# POWER.net
KiCad netlist of a schematic drawn in Altium Designer
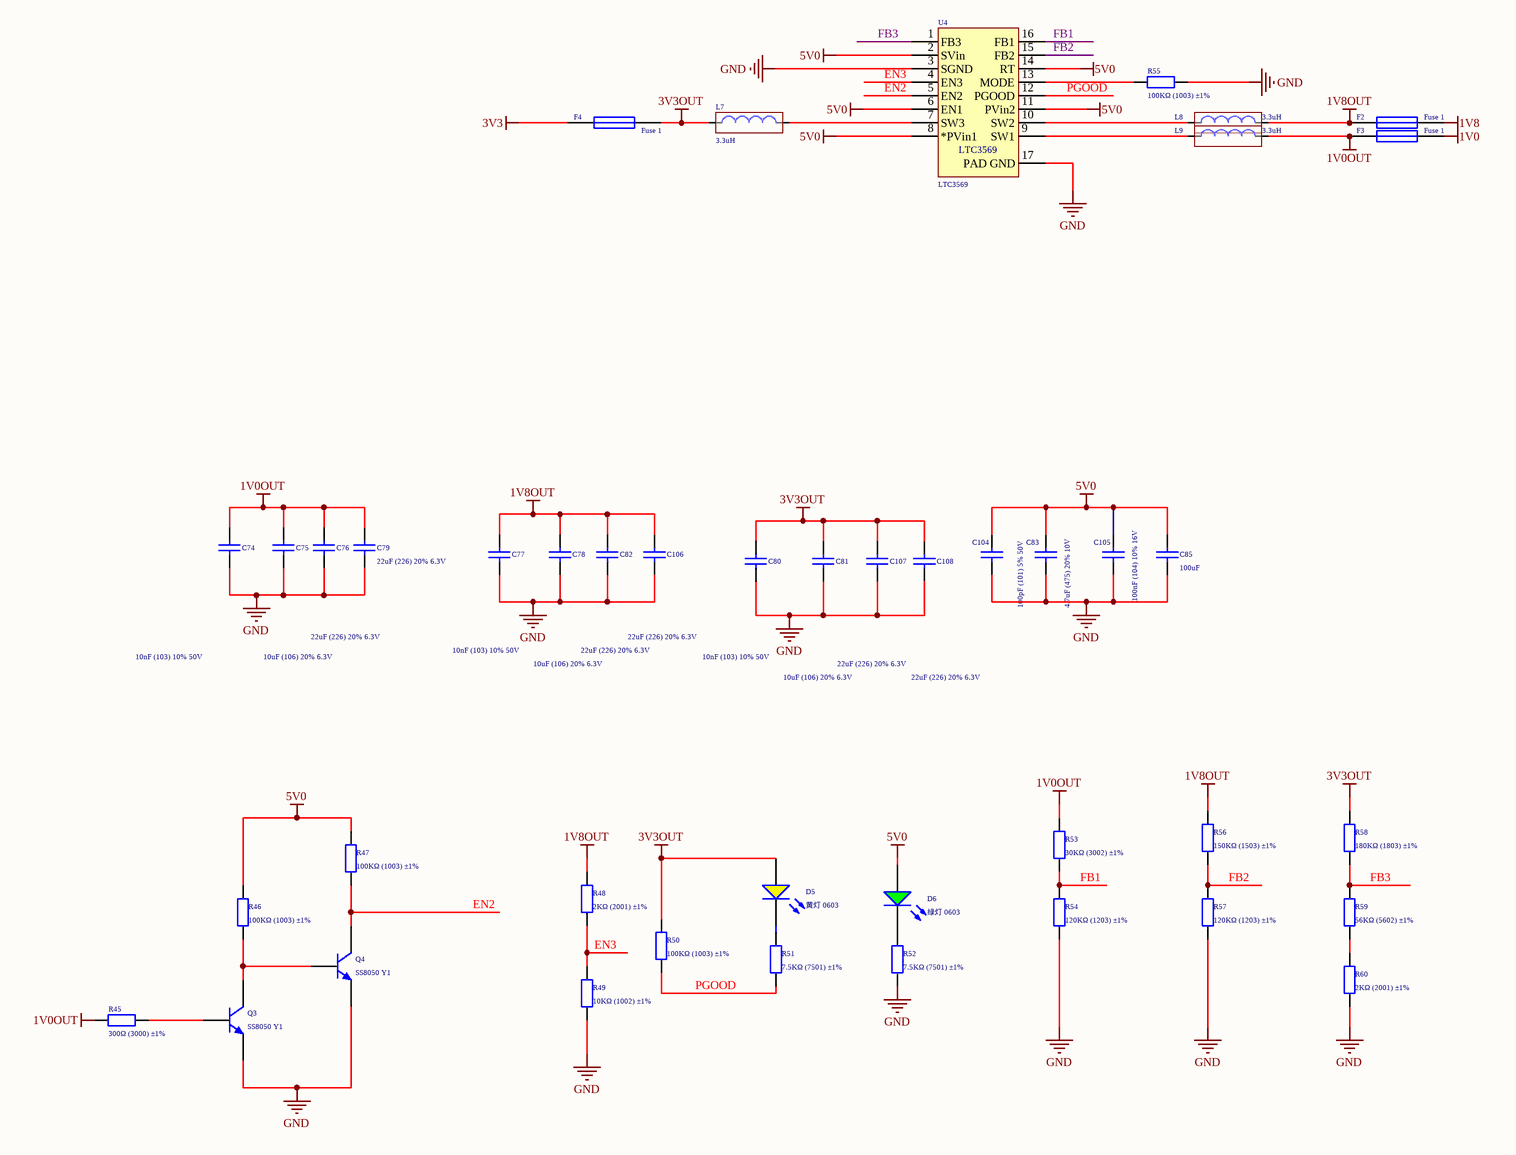
[diagram p0: POWER.SchDoc]

(export (version "E")
  (design (tool "Eeschema 10.0.6"))
  (components
    (comp (ref "C74")
      (value "10nF (103) 10% 50V")
      (footprint "0402_C")
      (description "贴片电容")
      (libsource (lib "Miscellaneous Devices LC") (part "0402 10nF (103) 10% 50V"))
    )
    (comp (ref "C75")
      (value "10uF (106) 20% 6.3V")
      (footprint "0402_C")
      (description "贴片电容")
      (libsource (lib "Miscellaneous Devices LC") (part "0402 10uF (106) 20% 6.3V"))
    )
    (comp (ref "C76")
      (value "22uF (226) 20% 6.3V")
      (footprint "0603_C")
      (description "贴片电容")
      (libsource (lib "Miscellaneous Devices LC") (part "0603 22uF (226) 20% 6.3V"))
    )
    (comp (ref "C77")
      (value "10nF (103) 10% 50V")
      (footprint "0402_C")
      (description "贴片电容")
      (libsource (lib "Miscellaneous Devices LC") (part "0402 10nF (103) 10% 50V"))
    )
    (comp (ref "C78")
      (value "10uF (106) 20% 6.3V")
      (footprint "0402_C")
      (description "贴片电容")
      (libsource (lib "Miscellaneous Devices LC") (part "0402 10uF (106) 20% 6.3V"))
    )
    (comp (ref "C79")
      (value "22uF (226) 20% 6.3V")
      (footprint "0603_C")
      (description "贴片电容")
      (libsource (lib "Miscellaneous Devices LC") (part "0603 22uF (226) 20% 6.3V"))
    )
    (comp (ref "C80")
      (value "10nF (103) 10% 50V")
      (footprint "0402_C")
      (description "贴片电容")
      (libsource (lib "Miscellaneous Devices LC") (part "0402 10nF (103) 10% 50V"))
    )
    (comp (ref "C81")
      (value "10uF (106) 20% 6.3V")
      (footprint "0402_C")
      (description "贴片电容")
      (libsource (lib "Miscellaneous Devices LC") (part "0402 10uF (106) 20% 6.3V"))
    )
    (comp (ref "C82")
      (value "22uF (226) 20% 6.3V")
      (footprint "0603_C")
      (description "贴片电容")
      (libsource (lib "Miscellaneous Devices LC") (part "0603 22uF (226) 20% 6.3V"))
    )
    (comp (ref "C83")
      (value "4.7uF (475) 20% 10V")
      (footprint "0402_C")
      (description "贴片电容")
      (libsource (lib "Miscellaneous Devices LC") (part "0402 4.7uF (475) 20% 10V"))
    )
    (comp (ref "C85")
      (value "100uF")
      (footprint "LC-1206")
      (description "贴片电容")
      (fields (field (name "Comment") "Cap") (field (name "PUBLISHER") "Altium Limited"))
      (libsource (lib "Sparks") (part "Cap"))
    )
    (comp (ref "C104")
      (value "100pF (101) 5% 50V")
      (footprint "0402_C")
      (description "贴片电容")
      (libsource (lib "Miscellaneous Devices LC") (part "0402 100pF (101) 5% 50V"))
    )
    (comp (ref "C105")
      (value "100nF (104) 10% 16V")
      (footprint "0402_C")
      (description "贴片电容")
      (libsource (lib "Miscellaneous Devices LC") (part "0402 100nF (104) 10% 16V"))
    )
    (comp (ref "C106")
      (value "22uF (226) 20% 6.3V")
      (footprint "0603_C")
      (description "贴片电容")
      (libsource (lib "Miscellaneous Devices LC") (part "0603 22uF (226) 20% 6.3V"))
    )
    (comp (ref "C107")
      (value "22uF (226) 20% 6.3V")
      (footprint "0603_C")
      (description "贴片电容")
      (libsource (lib "Miscellaneous Devices LC") (part "0603 22uF (226) 20% 6.3V"))
    )
    (comp (ref "C108")
      (value "22uF (226) 20% 6.3V")
      (footprint "0603_C")
      (description "贴片电容")
      (libsource (lib "Miscellaneous Devices LC") (part "0603 22uF (226) 20% 6.3V"))
    )
    (comp (ref "D5")
      (value "黄灯 0603")
      (footprint "0603_LED_S1")
      (description "发光二极管")
      (libsource (lib "Miscellaneous Devices LC") (part "0603 黄灯"))
    )
    (comp (ref "D6")
      (value "绿灯 0603")
      (footprint "0603_LED_S1")
      (description "发光二极管")
      (libsource (lib "Miscellaneous Devices LC") (part "0603 绿灯"))
    )
    (comp (ref "F2")
      (value "Fuse 1")
      (footprint "1206")
      (description "Fuse")
      (fields (field (name "PUBLISHER") "Altium Limited"))
      (libsource (lib "Miscellaneous Devices") (part "Fuse 1"))
    )
    (comp (ref "F3")
      (value "Fuse 1")
      (footprint "1206")
      (description "Fuse")
      (fields (field (name "PUBLISHER") "Altium Limited"))
      (libsource (lib "Miscellaneous Devices") (part "Fuse 1"))
    )
    (comp (ref "F4")
      (value "Fuse 1")
      (footprint "1206")
      (description "Fuse")
      (fields (field (name "PUBLISHER") "Altium Limited"))
      (libsource (lib "Miscellaneous Devices") (part "Fuse 1"))
    )
    (comp (ref "L7")
      (value "3.3uH")
      (footprint "LC-1210")
      (description "Inductor")
      (libsource (lib "2号库") (part "Inductor_1"))
    )
    (comp (ref "L8")
      (value "3.3uH")
      (footprint "LC-1210")
      (description "Inductor")
      (libsource (lib "2号库") (part "Inductor_1"))
    )
    (comp (ref "L9")
      (value "3.3uH")
      (footprint "LC-1210")
      (description "Inductor")
      (libsource (lib "2号库") (part "Inductor_1"))
    )
    (comp (ref "Q3")
      (value "SS8050 Y1")
      (footprint "SOT-23(SOT-23-3)")
      (description "三极管")
      (libsource (lib "Transistor_NPN") (part "SOT-23 SS8050 Y1"))
    )
    (comp (ref "Q4")
      (value "SS8050 Y1")
      (footprint "SOT-23(SOT-23-3)")
      (description "三极管")
      (libsource (lib "Transistor_NPN") (part "SOT-23 SS8050 Y1"))
    )
    (comp (ref "R45")
      (value "300Ω (3000) ±1%")
      (footprint "0402_R")
      (description "贴片电阻")
      (libsource (lib "Miscellaneous Devices LC") (part "0402 300Ω (3000) 1%"))
    )
    (comp (ref "R46")
      (value "100KΩ (1003) ±1%")
      (footprint "0402_R")
      (description "贴片电阻")
      (libsource (lib "Miscellaneous Devices LC") (part "0402 100KΩ (1003) 1%"))
    )
    (comp (ref "R47")
      (value "100KΩ (1003) ±1%")
      (footprint "0402_R")
      (description "贴片电阻")
      (libsource (lib "Miscellaneous Devices LC") (part "0402 100KΩ (1003) 1%"))
    )
    (comp (ref "R48")
      (value "2KΩ (2001) ±1%")
      (footprint "0402_R")
      (description "贴片电阻")
      (libsource (lib "Miscellaneous Devices LC") (part "0402 2KΩ (2001) 1%"))
    )
    (comp (ref "R49")
      (value "10KΩ (1002) ±1%")
      (footprint "0402_R")
      (description "贴片电阻")
      (libsource (lib "Miscellaneous Devices LC") (part "0402 10KΩ (1002) 1%"))
    )
    (comp (ref "R50")
      (value "100KΩ (1003) ±1%")
      (footprint "0402_R")
      (description "贴片电阻")
      (libsource (lib "Miscellaneous Devices LC") (part "0402 100KΩ (1003) 1%"))
    )
    (comp (ref "R51")
      (value "7.5KΩ (7501) ±1%")
      (footprint "0402_R")
      (description "贴片电阻")
      (libsource (lib "Miscellaneous Devices LC") (part "0402 7.5KΩ (7501) 1%"))
    )
    (comp (ref "R52")
      (value "7.5KΩ (7501) ±1%")
      (footprint "0402_R")
      (description "贴片电阻")
      (libsource (lib "Miscellaneous Devices LC") (part "0402 7.5KΩ (7501) 1%"))
    )
    (comp (ref "R53")
      (value "30KΩ (3002) ±1%")
      (footprint "0603_R")
      (description "贴片电阻")
      (libsource (lib "RES") (part "0603 30KΩ (3002) 1%"))
    )
    (comp (ref "R54")
      (value "120KΩ (1203) ±1%")
      (footprint "0402_R")
      (description "贴片电阻")
      (libsource (lib "Miscellaneous Devices LC") (part "0402 120KΩ (1203) 1%"))
    )
    (comp (ref "R55")
      (value "100KΩ (1003) ±1%")
      (footprint "0402_R")
      (description "贴片电阻")
      (libsource (lib "") (part "0402 100KΩ (1003) 1%_1"))
    )
    (comp (ref "R56")
      (value "150KΩ (1503) ±1%")
      (footprint "0402_R")
      (description "贴片电阻")
      (libsource (lib "Miscellaneous Devices LC") (part "0402 150KΩ (1503) 1%"))
    )
    (comp (ref "R57")
      (value "120KΩ (1203) ±1%")
      (footprint "0402_R")
      (description "贴片电阻")
      (libsource (lib "Miscellaneous Devices LC") (part "0402 120KΩ (1203) 1%"))
    )
    (comp (ref "R58")
      (value "180KΩ (1803) ±1%")
      (footprint "0603_R")
      (description "贴片电阻")
      (libsource (lib "Miscellaneous Devices LC") (part "0603 180KΩ (1803) 1%"))
    )
    (comp (ref "R59")
      (value "56KΩ (5602) ±1%")
      (footprint "0402_R")
      (description "贴片电阻")
      (libsource (lib "Miscellaneous Devices LC") (part "0402 56KΩ (5602) 1%"))
    )
    (comp (ref "R60")
      (value "2KΩ (2001) ±1%")
      (footprint "0402_R")
      (description "贴片电阻")
      (libsource (lib "Miscellaneous Devices LC") (part "0402 2KΩ (2001) 1%"))
    )
    (comp (ref "U4")
      (value "LTC3569")
      (footprint "SOP127P600-16N")
      (libsource (lib "Schlib") (part "LTC3569"))
    )
  )
  (nets
    (net (code "1") (name "/EN2") (class "Default")
      (node (ref "Q4") (pin "3") (pinfunction "C_3") (pintype "passive"))
      (node (ref "R47") (pin "1") (pinfunction "1_1") (pintype "passive"))
      (node (ref "U4") (pin "5") (pinfunction "EN2_5") (pintype "passive"))
    )
    (net (code "2") (name "/EN3") (class "Default")
      (node (ref "R48") (pin "1") (pinfunction "1_1") (pintype "passive"))
      (node (ref "R49") (pin "2") (pinfunction "2_2") (pintype "passive"))
      (node (ref "U4") (pin "4") (pinfunction "EN3_4") (pintype "passive"))
    )
    (net (code "3") (name "/FB1") (class "Default")
      (node (ref "R53") (pin "1") (pinfunction "1_1") (pintype "passive"))
      (node (ref "R54") (pin "2") (pinfunction "2_2") (pintype "passive"))
      (node (ref "U4") (pin "16") (pinfunction "FB1_16") (pintype "passive"))
    )
    (net (code "4") (name "/FB2") (class "Default")
      (node (ref "R56") (pin "1") (pinfunction "1_1") (pintype "passive"))
      (node (ref "R57") (pin "2") (pinfunction "2_2") (pintype "passive"))
      (node (ref "U4") (pin "15") (pinfunction "FB2_15") (pintype "passive"))
    )
    (net (code "5") (name "/FB3") (class "Default")
      (node (ref "R58") (pin "1") (pinfunction "1_1") (pintype "passive"))
      (node (ref "R59") (pin "2") (pinfunction "2_2") (pintype "passive"))
      (node (ref "U4") (pin "1") (pinfunction "FB3_1") (pintype "passive"))
    )
    (net (code "6") (name "/PGOOD") (class "Default")
      (node (ref "R50") (pin "1") (pinfunction "1_1") (pintype "passive"))
      (node (ref "R51") (pin "1") (pinfunction "1_1") (pintype "passive"))
      (node (ref "U4") (pin "12") (pinfunction "PGOOD_12") (pintype "passive"))
    )
    (net (code "7") (name "1V0") (class "Default")
      (node (ref "F3") (pin "1") (pinfunction "1_1") (pintype "passive"))
    )
    (net (code "8") (name "1V0OUT") (class "Default")
      (node (ref "C74") (pin "2") (pinfunction "2_2") (pintype "passive"))
      (node (ref "C75") (pin "2") (pinfunction "2_2") (pintype "passive"))
      (node (ref "C76") (pin "2") (pinfunction "2_2") (pintype "passive"))
      (node (ref "C79") (pin "2") (pinfunction "2_2") (pintype "passive"))
      (node (ref "F3") (pin "2") (pinfunction "2_2") (pintype "passive"))
      (node (ref "L9") (pin "2") (pinfunction "2_2") (pintype "passive"))
      (node (ref "R45") (pin "1") (pinfunction "1_1") (pintype "passive"))
      (node (ref "R53") (pin "2") (pinfunction "2_2") (pintype "passive"))
    )
    (net (code "9") (name "1V8") (class "Default")
      (node (ref "F2") (pin "1") (pinfunction "1_1") (pintype "passive"))
    )
    (net (code "10") (name "1V8OUT") (class "Default")
      (node (ref "C106") (pin "2") (pinfunction "2_2") (pintype "passive"))
      (node (ref "C77") (pin "2") (pinfunction "2_2") (pintype "passive"))
      (node (ref "C78") (pin "2") (pinfunction "2_2") (pintype "passive"))
      (node (ref "C82") (pin "2") (pinfunction "2_2") (pintype "passive"))
      (node (ref "F2") (pin "2") (pinfunction "2_2") (pintype "passive"))
      (node (ref "L8") (pin "2") (pinfunction "2_2") (pintype "passive"))
      (node (ref "R48") (pin "2") (pinfunction "2_2") (pintype "passive"))
      (node (ref "R56") (pin "2") (pinfunction "2_2") (pintype "passive"))
    )
    (net (code "11") (name "3V3") (class "Default")
      (node (ref "F4") (pin "2") (pinfunction "2_2") (pintype "passive"))
    )
    (net (code "12") (name "3V3OUT") (class "Default")
      (node (ref "C107") (pin "2") (pinfunction "2_2") (pintype "passive"))
      (node (ref "C108") (pin "2") (pinfunction "2_2") (pintype "passive"))
      (node (ref "C80") (pin "2") (pinfunction "2_2") (pintype "passive"))
      (node (ref "C81") (pin "2") (pinfunction "2_2") (pintype "passive"))
      (node (ref "D5") (pin "A") (pinfunction "A_A") (pintype "passive"))
      (node (ref "F4") (pin "1") (pinfunction "1_1") (pintype "passive"))
      (node (ref "L7") (pin "1") (pinfunction "1_1") (pintype "passive"))
      (node (ref "R50") (pin "2") (pinfunction "2_2") (pintype "passive"))
      (node (ref "R58") (pin "2") (pinfunction "2_2") (pintype "passive"))
    )
    (net (code "13") (name "5V0") (class "Default")
      (node (ref "C104") (pin "2") (pinfunction "2_2") (pintype "passive"))
      (node (ref "C105") (pin "2") (pinfunction "2_2") (pintype "passive"))
      (node (ref "C83") (pin "1") (pinfunction "1_1") (pintype "passive"))
      (node (ref "C85") (pin "2") (pinfunction "2_2") (pintype "passive"))
      (node (ref "D6") (pin "A") (pinfunction "A_A") (pintype "passive"))
      (node (ref "R46") (pin "2") (pinfunction "2_2") (pintype "passive"))
      (node (ref "R47") (pin "2") (pinfunction "2_2") (pintype "passive"))
      (node (ref "U4") (pin "11") (pinfunction "PVin2_11") (pintype "passive"))
      (node (ref "U4") (pin "14") (pinfunction "RT_14") (pintype "passive"))
      (node (ref "U4") (pin "2") (pinfunction "SVin_2") (pintype "passive"))
      (node (ref "U4") (pin "6") (pinfunction "EN1_6") (pintype "passive"))
      (node (ref "U4") (pin "8") (pinfunction "*PVin1_8") (pintype "passive"))
    )
    (net (code "14") (name "GND") (class "Default")
      (node (ref "C104") (pin "1") (pinfunction "1_1") (pintype "passive"))
      (node (ref "C105") (pin "1") (pinfunction "1_1") (pintype "passive"))
      (node (ref "C106") (pin "1") (pinfunction "1_1") (pintype "passive"))
      (node (ref "C107") (pin "1") (pinfunction "1_1") (pintype "passive"))
      (node (ref "C108") (pin "1") (pinfunction "1_1") (pintype "passive"))
      (node (ref "C74") (pin "1") (pinfunction "1_1") (pintype "passive"))
      (node (ref "C75") (pin "1") (pinfunction "1_1") (pintype "passive"))
      (node (ref "C76") (pin "1") (pinfunction "1_1") (pintype "passive"))
      (node (ref "C77") (pin "1") (pinfunction "1_1") (pintype "passive"))
      (node (ref "C78") (pin "1") (pinfunction "1_1") (pintype "passive"))
      (node (ref "C79") (pin "1") (pinfunction "1_1") (pintype "passive"))
      (node (ref "C80") (pin "1") (pinfunction "1_1") (pintype "passive"))
      (node (ref "C81") (pin "1") (pinfunction "1_1") (pintype "passive"))
      (node (ref "C82") (pin "1") (pinfunction "1_1") (pintype "passive"))
      (node (ref "C83") (pin "2") (pinfunction "2_2") (pintype "passive"))
      (node (ref "C85") (pin "1") (pinfunction "1_1") (pintype "passive"))
      (node (ref "Q3") (pin "2") (pinfunction "E_2") (pintype "passive"))
      (node (ref "Q4") (pin "2") (pinfunction "E_2") (pintype "passive"))
      (node (ref "R49") (pin "1") (pinfunction "1_1") (pintype "passive"))
      (node (ref "R52") (pin "1") (pinfunction "1_1") (pintype "passive"))
      (node (ref "R54") (pin "1") (pinfunction "1_1") (pintype "passive"))
      (node (ref "R55") (pin "2") (pinfunction "2_2") (pintype "passive"))
      (node (ref "R57") (pin "1") (pinfunction "1_1") (pintype "passive"))
      (node (ref "R60") (pin "1") (pinfunction "1_1") (pintype "passive"))
      (node (ref "U4") (pin "17") (pinfunction "PAD_GND_17") (pintype "passive"))
      (node (ref "U4") (pin "3") (pinfunction "SGND_3") (pintype "passive"))
    )
    (net (code "15") (name "Net-(D5-PadK)") (class "Default")
      (node (ref "D5") (pin "K") (pinfunction "K_K") (pintype "passive"))
      (node (ref "R51") (pin "2") (pinfunction "2_2") (pintype "passive"))
    )
    (net (code "16") (name "Net-(D6-PadK)") (class "Default")
      (node (ref "D6") (pin "K") (pinfunction "K_K") (pintype "passive"))
      (node (ref "R52") (pin "2") (pinfunction "2_2") (pintype "passive"))
    )
    (net (code "17") (name "Net-(Q3-B)") (class "Default")
      (node (ref "Q3") (pin "1") (pinfunction "B_1") (pintype "passive"))
      (node (ref "R45") (pin "2") (pinfunction "2_2") (pintype "passive"))
    )
    (net (code "18") (name "Net-(Q3-C)") (class "Default")
      (node (ref "Q3") (pin "3") (pinfunction "C_3") (pintype "passive"))
      (node (ref "Q4") (pin "1") (pinfunction "B_1") (pintype "passive"))
      (node (ref "R46") (pin "1") (pinfunction "1_1") (pintype "passive"))
    )
    (net (code "19") (name "Net-(R59-Pad1)") (class "Default")
      (node (ref "R59") (pin "1") (pinfunction "1_1") (pintype "passive"))
      (node (ref "R60") (pin "2") (pinfunction "2_2") (pintype "passive"))
    )
    (net (code "20") (name "Net-(U4-MODE)") (class "Default")
      (node (ref "R55") (pin "1") (pinfunction "1_1") (pintype "passive"))
      (node (ref "U4") (pin "13") (pinfunction "MODE_13") (pintype "passive"))
    )
    (net (code "21") (name "Net-(U4-SW1)") (class "Default")
      (node (ref "L9") (pin "1") (pinfunction "1_1") (pintype "passive"))
      (node (ref "U4") (pin "9") (pinfunction "SW1_9") (pintype "passive"))
    )
    (net (code "22") (name "Net-(U4-SW2)") (class "Default")
      (node (ref "L8") (pin "1") (pinfunction "1_1") (pintype "passive"))
      (node (ref "U4") (pin "10") (pinfunction "SW2_10") (pintype "passive"))
    )
    (net (code "23") (name "Net-(U4-SW3)") (class "Default")
      (node (ref "L7") (pin "2") (pinfunction "2_2") (pintype "passive"))
      (node (ref "U4") (pin "7") (pinfunction "SW3_7") (pintype "passive"))
    )
  )
)
